# ATMEGA16.net
KiCad netlist of a schematic drawn in Altium Designer
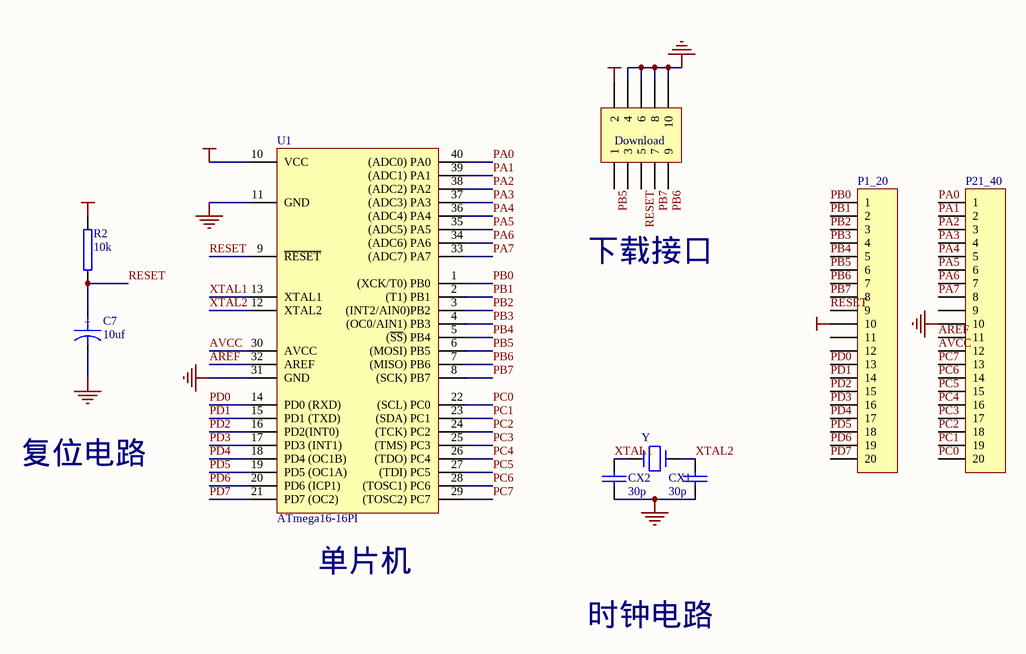
[diagram p0: ATMEGA16单片机模块.SCHDOC]

(export (version "E")
  (design (tool "Eeschema 10.0.6"))
  (components
    (comp (ref "C7")
      (value "10uf")
      (footprint "C-DJ-4")
      (description "Capacitor")
      (libsource (lib "*") (part "CAPACITOR POL"))
    )
    (comp (ref "CX1")
      (value "30p")
      (footprint "HDR1X2")
      (description "Capacitor")
      (libsource (lib "*") (part "CAP"))
    )
    (comp (ref "CX2")
      (value "30p")
      (footprint "HDR1X2")
      (description "Capacitor")
      (libsource (lib "*") (part "CAP"))
    )
    (comp (ref "Download")
      (value "Download")
      (footprint "HDR-2x5")
      (description "Header, 5-Pin, Dual row")
      (fields (field (name "PUBLISHER") "Altium Limited"))
      (libsource (lib "Miscellaneous Connectors") (part "Header 5X2"))
    )
    (comp (ref "P1_20")
      (value "PZ_20")
      (footprint "HDR1X20")
      (description "排针——20")
      (fields (field (name "PUBLISHER") "Altium Limited"))
      (libsource (lib "zxcourhc") (part "PZ_20"))
    )
    (comp (ref "P21_40")
      (value "PZ_20")
      (footprint "HDR1X20")
      (description "排针——20")
      (fields (field (name "PUBLISHER") "Altium Limited"))
      (libsource (lib "zxcourhc") (part "PZ_20"))
    )
    (comp (ref "R2") (value "10k") (footprint "RSE") (libsource (lib "*") (part "RES2")))
    (comp (ref "U1")
      (value "ATmega16-16PI")
      (footprint "底座DIP-40/引脚15.24mm")
      (description "8 位微处理器/40引脚")
      (fields (field (name "发布者") "磊元工作室"))
      (libsource (lib "微控制处理器") (part "ATmega16-P"))
    )
    (comp (ref "Y")
      (value "Y")
      (footprint "JZ_ZC")
      (description "Crystal")
      (libsource (lib "*") (part "CRYSTAL"))
    )
  )
  (nets
    (net (code "1") (name "/AREF") (class "Default")
      (node (ref "P21_40") (pin "11") (pinfunction "11_11") (pintype "passive"))
      (node (ref "U1") (pin "32") (pinfunction "AREF_32") (pintype "passive"))
    )
    (net (code "2") (name "/AVCC") (class "Default")
      (node (ref "P21_40") (pin "12") (pinfunction "12_12") (pintype "passive"))
      (node (ref "U1") (pin "30") (pinfunction "AVCC_30") (pintype "passive"))
    )
    (net (code "3") (name "/PA0") (class "Default")
      (node (ref "P21_40") (pin "1") (pinfunction "1_1") (pintype "passive"))
      (node (ref "U1") (pin "40") (pinfunction "(ADC0)_PA0_40") (pintype "passive"))
    )
    (net (code "4") (name "/PA1") (class "Default")
      (node (ref "P21_40") (pin "2") (pinfunction "2_2") (pintype "passive"))
      (node (ref "U1") (pin "39") (pinfunction "(ADC1)_PA1_39") (pintype "passive"))
    )
    (net (code "5") (name "/PA2") (class "Default")
      (node (ref "P21_40") (pin "3") (pinfunction "3_3") (pintype "passive"))
      (node (ref "U1") (pin "38") (pinfunction "(ADC2)_PA2_38") (pintype "passive"))
    )
    (net (code "6") (name "/PA3") (class "Default")
      (node (ref "P21_40") (pin "4") (pinfunction "4_4") (pintype "passive"))
      (node (ref "U1") (pin "37") (pinfunction "(ADC3)_PA3_37") (pintype "passive"))
    )
    (net (code "7") (name "/PA4") (class "Default")
      (node (ref "P21_40") (pin "5") (pinfunction "5_5") (pintype "passive"))
      (node (ref "U1") (pin "36") (pinfunction "(ADC4)_PA4_36") (pintype "passive"))
    )
    (net (code "8") (name "/PA5") (class "Default")
      (node (ref "P21_40") (pin "6") (pinfunction "6_6") (pintype "passive"))
      (node (ref "U1") (pin "35") (pinfunction "(ADC5)_PA5_35") (pintype "passive"))
    )
    (net (code "9") (name "/PA6") (class "Default")
      (node (ref "P21_40") (pin "7") (pinfunction "7_7") (pintype "passive"))
      (node (ref "U1") (pin "34") (pinfunction "(ADC6)_PA6_34") (pintype "passive"))
    )
    (net (code "10") (name "/PA7") (class "Default")
      (node (ref "P21_40") (pin "8") (pinfunction "8_8") (pintype "passive"))
      (node (ref "U1") (pin "33") (pinfunction "(ADC7)_PA7_33") (pintype "passive"))
    )
    (net (code "11") (name "/PB0") (class "Default")
      (node (ref "P1_20") (pin "1") (pinfunction "1_1") (pintype "passive"))
      (node (ref "U1") (pin "1") (pinfunction "(XCK/T0)_PB0_1") (pintype "passive"))
    )
    (net (code "12") (name "/PB1") (class "Default")
      (node (ref "P1_20") (pin "2") (pinfunction "2_2") (pintype "passive"))
      (node (ref "U1") (pin "2") (pinfunction "(T1)_PB1_2") (pintype "passive"))
    )
    (net (code "13") (name "/PB2") (class "Default")
      (node (ref "P1_20") (pin "3") (pinfunction "3_3") (pintype "passive"))
      (node (ref "U1") (pin "3") (pinfunction "(INT2/AIN0)PB2_3") (pintype "passive"))
    )
    (net (code "14") (name "/PB3") (class "Default")
      (node (ref "P1_20") (pin "4") (pinfunction "4_4") (pintype "passive"))
      (node (ref "U1") (pin "4") (pinfunction "(OC0/AIN1)_PB3_4") (pintype "passive"))
    )
    (net (code "15") (name "/PB4") (class "Default")
      (node (ref "P1_20") (pin "5") (pinfunction "5_5") (pintype "passive"))
      (node (ref "U1") (pin "5") (pinfunction "(~{SS})_PB4_5") (pintype "passive"))
    )
    (net (code "16") (name "/PB5") (class "Default")
      (node (ref "Download") (pin "1") (pinfunction "1_1") (pintype "passive"))
      (node (ref "P1_20") (pin "6") (pinfunction "6_6") (pintype "passive"))
      (node (ref "U1") (pin "6") (pinfunction "(MOSI)_PB5_6") (pintype "passive"))
    )
    (net (code "17") (name "/PB6") (class "Default")
      (node (ref "Download") (pin "9") (pinfunction "9_9") (pintype "passive"))
      (node (ref "P1_20") (pin "7") (pinfunction "7_7") (pintype "passive"))
      (node (ref "U1") (pin "7") (pinfunction "(MISO)_PB6_7") (pintype "passive"))
    )
    (net (code "18") (name "/PB7") (class "Default")
      (node (ref "Download") (pin "7") (pinfunction "7_7") (pintype "passive"))
      (node (ref "P1_20") (pin "8") (pinfunction "8_8") (pintype "passive"))
      (node (ref "U1") (pin "8") (pinfunction "(SCK)_PB7_8") (pintype "passive"))
    )
    (net (code "19") (name "/PC0") (class "Default")
      (node (ref "P21_40") (pin "20") (pinfunction "20_20") (pintype "passive"))
      (node (ref "U1") (pin "22") (pinfunction "(SCL)_PC0_22") (pintype "passive"))
    )
    (net (code "20") (name "/PC1") (class "Default")
      (node (ref "P21_40") (pin "19") (pinfunction "19_19") (pintype "passive"))
      (node (ref "U1") (pin "23") (pinfunction "(SDA)_PC1_23") (pintype "passive"))
    )
    (net (code "21") (name "/PC2") (class "Default")
      (node (ref "P21_40") (pin "18") (pinfunction "18_18") (pintype "passive"))
      (node (ref "U1") (pin "24") (pinfunction "(TCK)_PC2_24") (pintype "passive"))
    )
    (net (code "22") (name "/PC3") (class "Default")
      (node (ref "P21_40") (pin "17") (pinfunction "17_17") (pintype "passive"))
      (node (ref "U1") (pin "25") (pinfunction "(TMS)_PC3_25") (pintype "passive"))
    )
    (net (code "23") (name "/PC4") (class "Default")
      (node (ref "P21_40") (pin "16") (pinfunction "16_16") (pintype "passive"))
      (node (ref "U1") (pin "26") (pinfunction "(TDO)_PC4_26") (pintype "passive"))
    )
    (net (code "24") (name "/PC5") (class "Default")
      (node (ref "P21_40") (pin "15") (pinfunction "15_15") (pintype "passive"))
      (node (ref "U1") (pin "27") (pinfunction "(TDI)_PC5_27") (pintype "passive"))
    )
    (net (code "25") (name "/PC6") (class "Default")
      (node (ref "P21_40") (pin "14") (pinfunction "14_14") (pintype "passive"))
      (node (ref "U1") (pin "28") (pinfunction "(TOSC1)_PC6_28") (pintype "passive"))
    )
    (net (code "26") (name "/PC7") (class "Default")
      (node (ref "P21_40") (pin "13") (pinfunction "13_13") (pintype "passive"))
      (node (ref "U1") (pin "29") (pinfunction "(TOSC2)_PC7_29") (pintype "passive"))
    )
    (net (code "27") (name "/PD0") (class "Default")
      (node (ref "P1_20") (pin "13") (pinfunction "13_13") (pintype "passive"))
      (node (ref "U1") (pin "14") (pinfunction "PD0_(RXD)_14") (pintype "passive"))
    )
    (net (code "28") (name "/PD1") (class "Default")
      (node (ref "P1_20") (pin "14") (pinfunction "14_14") (pintype "passive"))
      (node (ref "U1") (pin "15") (pinfunction "PD1_(TXD)_15") (pintype "passive"))
    )
    (net (code "29") (name "/PD2") (class "Default")
      (node (ref "P1_20") (pin "15") (pinfunction "15_15") (pintype "passive"))
      (node (ref "U1") (pin "16") (pinfunction "PD2(INT0)_16") (pintype "passive"))
    )
    (net (code "30") (name "/PD3") (class "Default")
      (node (ref "P1_20") (pin "16") (pinfunction "16_16") (pintype "passive"))
      (node (ref "U1") (pin "17") (pinfunction "PD3_(INT1)_17") (pintype "passive"))
    )
    (net (code "31") (name "/PD4") (class "Default")
      (node (ref "P1_20") (pin "17") (pinfunction "17_17") (pintype "passive"))
      (node (ref "U1") (pin "18") (pinfunction "PD4_(OC1B)_18") (pintype "passive"))
    )
    (net (code "32") (name "/PD5") (class "Default")
      (node (ref "P1_20") (pin "18") (pinfunction "18_18") (pintype "passive"))
      (node (ref "U1") (pin "19") (pinfunction "PD5_(OC1A)_19") (pintype "passive"))
    )
    (net (code "33") (name "/PD6") (class "Default")
      (node (ref "P1_20") (pin "19") (pinfunction "19_19") (pintype "passive"))
      (node (ref "U1") (pin "20") (pinfunction "PD6_(ICP1)_20") (pintype "passive"))
    )
    (net (code "34") (name "/PD7") (class "Default")
      (node (ref "P1_20") (pin "20") (pinfunction "20_20") (pintype "passive"))
      (node (ref "U1") (pin "21") (pinfunction "PD7_(OC2)_21") (pintype "passive"))
    )
    (net (code "35") (name "/RESET") (class "Default")
      (node (ref "C7") (pin "1") (pinfunction "1_1") (pintype "passive"))
      (node (ref "Download") (pin "5") (pinfunction "5_5") (pintype "passive"))
      (node (ref "P1_20") (pin "9") (pinfunction "9_9") (pintype "passive"))
      (node (ref "R2") (pin "1") (pinfunction "1_1") (pintype "passive"))
      (node (ref "U1") (pin "9") (pinfunction "~{RESET}_9") (pintype "passive"))
    )
    (net (code "36") (name "/XTAL1") (class "Default")
      (node (ref "CX2") (pin "1") (pinfunction "1_1") (pintype "passive"))
      (node (ref "U1") (pin "13") (pinfunction "XTAL1_13") (pintype "passive"))
      (node (ref "Y") (pin "2") (pinfunction "2_2") (pintype "passive"))
    )
    (net (code "37") (name "/XTAL2") (class "Default")
      (node (ref "CX1") (pin "1") (pinfunction "1_1") (pintype "passive"))
      (node (ref "U1") (pin "12") (pinfunction "XTAL2_12") (pintype "passive"))
      (node (ref "Y") (pin "1") (pinfunction "1_1") (pintype "passive"))
    )
    (net (code "38") (name "GND") (class "Default")
      (node (ref "C7") (pin "2") (pinfunction "2_2") (pintype "passive"))
      (node (ref "CX1") (pin "2") (pinfunction "2_2") (pintype "passive"))
      (node (ref "CX2") (pin "2") (pinfunction "2_2") (pintype "passive"))
      (node (ref "Download") (pin "10") (pinfunction "10_10") (pintype "passive"))
      (node (ref "Download") (pin "4") (pinfunction "4_4") (pintype "passive"))
      (node (ref "Download") (pin "6") (pinfunction "6_6") (pintype "passive"))
      (node (ref "Download") (pin "8") (pinfunction "8_8") (pintype "passive"))
      (node (ref "P21_40") (pin "10") (pinfunction "10_10") (pintype "passive"))
      (node (ref "U1") (pin "11") (pinfunction "GND_11") (pintype "passive"))
      (node (ref "U1") (pin "31") (pinfunction "GND_31") (pintype "passive"))
    )
    (net (code "39") (name "VCC") (class "Default")
      (node (ref "Download") (pin "2") (pinfunction "2_2") (pintype "passive"))
      (node (ref "P1_20") (pin "10") (pinfunction "10_10") (pintype "passive"))
      (node (ref "R2") (pin "2") (pinfunction "2_2") (pintype "passive"))
      (node (ref "U1") (pin "10") (pinfunction "VCC_10") (pintype "passive"))
    )
    (net (code "40") (name "unconnected-(Download-Pad3)") (class "Default")
      (node (ref "Download") (pin "3") (pinfunction "3_3") (pintype "passive"))
    )
    (net (code "41") (name "unconnected-(P1_20-Pad11)") (class "Default")
      (node (ref "P1_20") (pin "11") (pinfunction "11_11") (pintype "passive"))
    )
    (net (code "42") (name "unconnected-(P1_20-Pad12)") (class "Default")
      (node (ref "P1_20") (pin "12") (pinfunction "12_12") (pintype "passive"))
    )
    (net (code "43") (name "unconnected-(P21_40-Pad9)") (class "Default")
      (node (ref "P21_40") (pin "9") (pinfunction "9_9") (pintype "passive"))
    )
  )
)
